# BipolarDAC_16-bit_v01.net
KiCad netlist of a schematic drawn in EAGLE
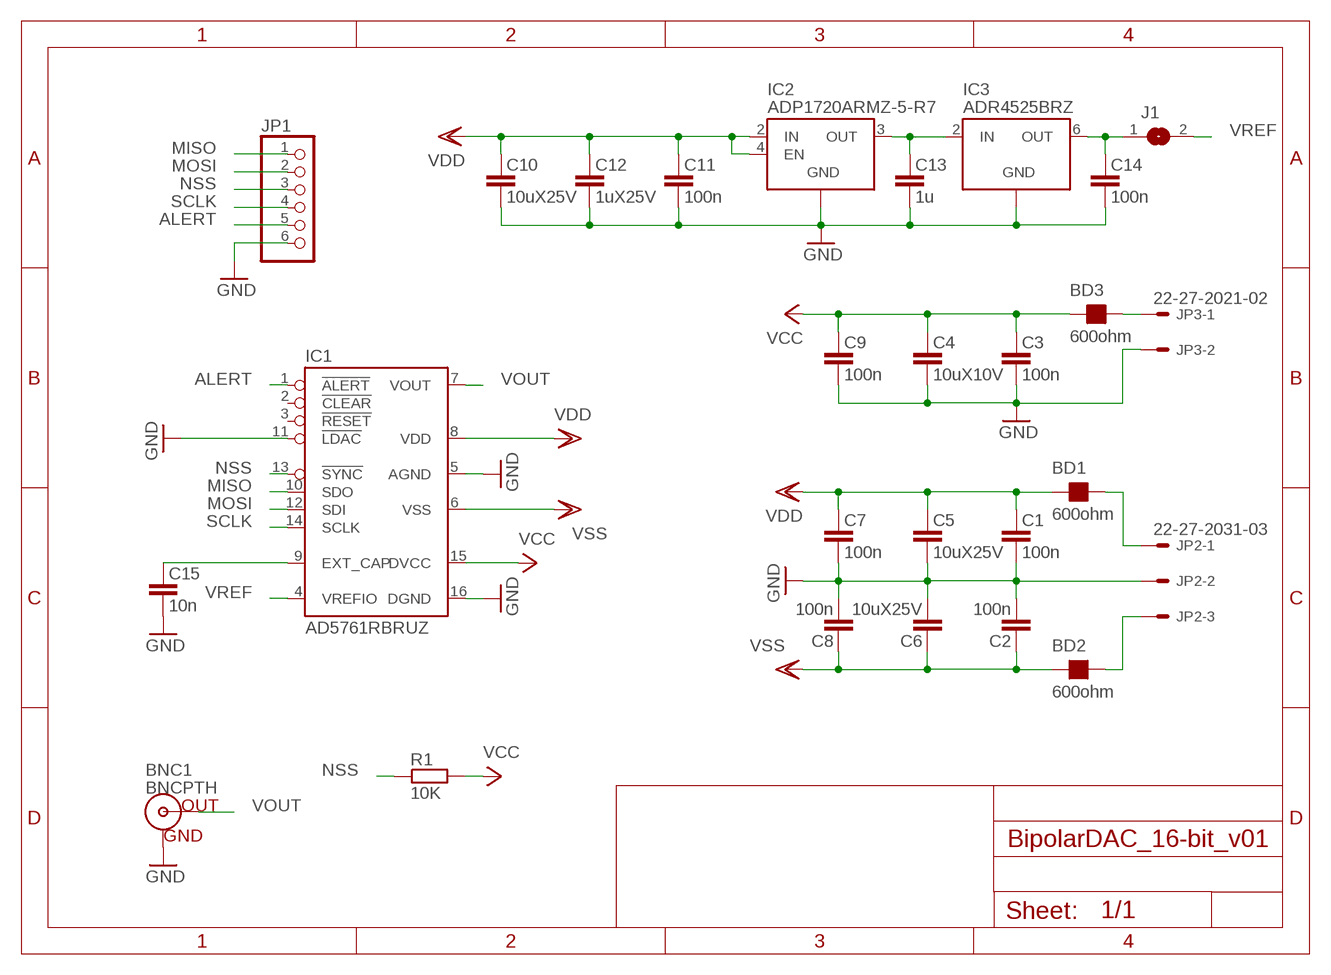
[diagram p0: schematic, sheet 1]

(export (version "E")
  (design (tool "Eeschema 10.0.6"))
  (components
    (comp (ref "BD1")
      (value "600ohm")
      (footprint "eagle-import:L0805")
      (libsource (lib "eagle-import") (part "FB_0805"))
    )
    (comp (ref "BD2")
      (value "600ohm")
      (footprint "eagle-import:L0805")
      (libsource (lib "eagle-import") (part "FB_0805"))
    )
    (comp (ref "BD3")
      (value "600ohm")
      (footprint "eagle-import:L0805")
      (libsource (lib "eagle-import") (part "FB_0805"))
    )
    (comp (ref "BNC1")
      (value "BNCPTH")
      (footprint "eagle-import:BNC")
      (libsource (lib "eagle-import") (part "BNCPTH"))
    )
    (comp (ref "C1")
      (value "100n")
      (footprint "eagle-import:C0603G")
      (libsource (lib "eagle-import") (part "C_EU_C0603G"))
    )
    (comp (ref "C2")
      (value "100n")
      (footprint "eagle-import:C0603G")
      (libsource (lib "eagle-import") (part "C_EU_C0603G"))
    )
    (comp (ref "C3")
      (value "100n")
      (footprint "eagle-import:C0402G")
      (libsource (lib "eagle-import") (part "C_EU_C0402G"))
    )
    (comp (ref "C4")
      (value "10uX10V")
      (footprint "eagle-import:C0805G")
      (libsource (lib "eagle-import") (part "C_EU_C0805G"))
    )
    (comp (ref "C5")
      (value "10uX25V")
      (footprint "eagle-import:C1206G")
      (libsource (lib "eagle-import") (part "C_EU_C1206G"))
    )
    (comp (ref "C6")
      (value "10uX25V")
      (footprint "eagle-import:C1206G")
      (libsource (lib "eagle-import") (part "C_EU_C1206G"))
    )
    (comp (ref "C7")
      (value "100n")
      (footprint "eagle-import:C0603G")
      (libsource (lib "eagle-import") (part "C_EU_C0603G"))
    )
    (comp (ref "C8")
      (value "100n")
      (footprint "eagle-import:C0603G")
      (libsource (lib "eagle-import") (part "C_EU_C0603G"))
    )
    (comp (ref "C9")
      (value "100n")
      (footprint "eagle-import:C0402G")
      (libsource (lib "eagle-import") (part "C_EU_C0402G"))
    )
    (comp (ref "C10")
      (value "10uX25V")
      (footprint "eagle-import:C1206G")
      (libsource (lib "eagle-import") (part "C_EU_C1206G"))
    )
    (comp (ref "C11")
      (value "100n")
      (footprint "eagle-import:C0603G")
      (libsource (lib "eagle-import") (part "C_EU_C0603G"))
    )
    (comp (ref "C12")
      (value "1uX25V")
      (footprint "eagle-import:C0603G")
      (libsource (lib "eagle-import") (part "C_EU_C0603G"))
    )
    (comp (ref "C13")
      (value "1u")
      (footprint "eagle-import:C0603G")
      (libsource (lib "eagle-import") (part "C_EU_C0603G"))
    )
    (comp (ref "C14")
      (value "100n")
      (footprint "eagle-import:C0603G")
      (libsource (lib "eagle-import") (part "C_EU_C0603G"))
    )
    (comp (ref "C15")
      (value "10n")
      (footprint "eagle-import:C0603G")
      (libsource (lib "eagle-import") (part "C_EU_C0603G"))
    )
    (comp (ref "IC1")
      (value "AD5761RBRUZ")
      (footprint "eagle-import:TSSOP16")
      (libsource (lib "eagle-import") (part "AD5761RBRUZ"))
    )
    (comp (ref "IC2")
      (value "ADP1720ARMZ-5-R7")
      (footprint "eagle-import:MSOP8")
      (libsource (lib "eagle-import") (part "ADP1720ARMZ-5-R7"))
    )
    (comp (ref "IC3")
      (value "ADR4525BRZ")
      (footprint "eagle-import:SOIC-8")
      (libsource (lib "eagle-import") (part "ADR4525BRZ"))
    )
    (comp (ref "J1")
      (value "SJS")
      (footprint "eagle-import:SJS")
      (libsource (lib "eagle-import") (part "SJS"))
    )
    (comp (ref "JP1")
      (value "PINHD-1X6")
      (footprint "eagle-import:1X06")
      (libsource (lib "eagle-import") (part "PINHD-1X6"))
    )
    (comp (ref "JP2")
      (value "22-27-2031-03")
      (footprint "eagle-import:6410-03")
      (libsource (lib "eagle-import") (part "22-?-0327-2031"))
    )
    (comp (ref "JP3")
      (value "22-27-2021-02")
      (footprint "eagle-import:6410-02")
      (libsource (lib "eagle-import") (part "22-?-0227-2021"))
    )
    (comp (ref "R1")
      (value "10K")
      (footprint "eagle-import:R0603G")
      (libsource (lib "eagle-import") (part "R_EU_R0603G"))
    )
  )
  (nets
    (net (code "1") (name "/ALERT") (class "Default")
      (node (ref "IC1") (pin "1") (pinfunction "~{ALERT}_1") (pintype "output"))
      (node (ref "JP1") (pin "5") (pinfunction "5_5") (pintype "passive"))
    )
    (net (code "2") (name "/MISO") (class "Default")
      (node (ref "IC1") (pin "10") (pinfunction "SDO_10") (pintype "output"))
      (node (ref "JP1") (pin "1") (pinfunction "1_1") (pintype "passive"))
    )
    (net (code "3") (name "/MOSI") (class "Default")
      (node (ref "IC1") (pin "12") (pinfunction "SDI_12") (pintype "input"))
      (node (ref "JP1") (pin "2") (pinfunction "2_2") (pintype "passive"))
    )
    (net (code "4") (name "/NSS") (class "Default")
      (node (ref "IC1") (pin "13") (pinfunction "~{SYNC}_13") (pintype "input"))
      (node (ref "JP1") (pin "3") (pinfunction "3_3") (pintype "passive"))
      (node (ref "R1") (pin "1") (pinfunction "1_1") (pintype "passive"))
    )
    (net (code "5") (name "/SCLK") (class "Default")
      (node (ref "IC1") (pin "14") (pinfunction "SCLK_14") (pintype "input"))
      (node (ref "JP1") (pin "4") (pinfunction "4_4") (pintype "passive"))
    )
    (net (code "6") (name "/VOUT") (class "Default")
      (node (ref "BNC1") (pin "S") (pinfunction "OUT_S") (pintype "bidirectional"))
      (node (ref "IC1") (pin "7") (pinfunction "VOUT_7") (pintype "output"))
    )
    (net (code "7") (name "/VREF") (class "Default")
      (node (ref "IC1") (pin "4") (pinfunction "VREFIO_4") (pintype "bidirectional"))
      (node (ref "J1") (pin "2") (pinfunction "2_2") (pintype "passive"))
    )
    (net (code "8") (name "GND") (class "Default")
      (node (ref "BNC1") (pin "GND") (pinfunction "GND_GND") (pintype "bidirectional"))
      (node (ref "C1") (pin "2") (pinfunction "2_2") (pintype "passive"))
      (node (ref "C10") (pin "2") (pinfunction "2_2") (pintype "passive"))
      (node (ref "C11") (pin "2") (pinfunction "2_2") (pintype "passive"))
      (node (ref "C12") (pin "2") (pinfunction "2_2") (pintype "passive"))
      (node (ref "C13") (pin "2") (pinfunction "2_2") (pintype "passive"))
      (node (ref "C14") (pin "2") (pinfunction "2_2") (pintype "passive"))
      (node (ref "C15") (pin "2") (pinfunction "2_2") (pintype "passive"))
      (node (ref "C2") (pin "2") (pinfunction "2_2") (pintype "passive"))
      (node (ref "C3") (pin "2") (pinfunction "2_2") (pintype "passive"))
      (node (ref "C4") (pin "2") (pinfunction "2_2") (pintype "passive"))
      (node (ref "C5") (pin "2") (pinfunction "2_2") (pintype "passive"))
      (node (ref "C6") (pin "2") (pinfunction "2_2") (pintype "passive"))
      (node (ref "C7") (pin "2") (pinfunction "2_2") (pintype "passive"))
      (node (ref "C8") (pin "2") (pinfunction "2_2") (pintype "passive"))
      (node (ref "C9") (pin "2") (pinfunction "2_2") (pintype "passive"))
      (node (ref "IC1") (pin "11") (pinfunction "~{LDAC}_11") (pintype "input"))
      (node (ref "IC1") (pin "16") (pinfunction "DGND_16") (pintype "power_in"))
      (node (ref "IC1") (pin "5") (pinfunction "AGND_5") (pintype "power_in"))
      (node (ref "IC2") (pin "1") (pinfunction "GND_1") (pintype "power_in"))
      (node (ref "IC2") (pin "5") (pinfunction "GND_5") (pintype "power_in"))
      (node (ref "IC2") (pin "6") (pinfunction "GND_6") (pintype "power_in"))
      (node (ref "IC2") (pin "7") (pinfunction "GND_7") (pintype "power_in"))
      (node (ref "IC2") (pin "8") (pinfunction "GND_8") (pintype "power_in"))
      (node (ref "IC3") (pin "4") (pinfunction "GND_4") (pintype "power_in"))
      (node (ref "JP1") (pin "6") (pinfunction "6_6") (pintype "passive"))
      (node (ref "JP2") (pin "2") (pinfunction "S_2") (pintype "passive"))
      (node (ref "JP3") (pin "2") (pinfunction "S_2") (pintype "passive"))
    )
    (net (code "9") (name "Net-(IC1-EXT_CAP)") (class "Default")
      (node (ref "C15") (pin "1") (pinfunction "1_1") (pintype "passive"))
      (node (ref "IC1") (pin "9") (pinfunction "EXT_CAP_9") (pintype "output"))
    )
    (net (code "10") (name "Net-(IC2-OUT)") (class "Default")
      (node (ref "C13") (pin "1") (pinfunction "1_1") (pintype "passive"))
      (node (ref "IC2") (pin "3") (pinfunction "OUT_3") (pintype "power_in"))
      (node (ref "IC3") (pin "2") (pinfunction "IN_2") (pintype "power_in"))
    )
    (net (code "11") (name "Net-(IC3-OUT)") (class "Default")
      (node (ref "C14") (pin "1") (pinfunction "1_1") (pintype "passive"))
      (node (ref "IC3") (pin "6") (pinfunction "OUT_6") (pintype "power_in"))
      (node (ref "J1") (pin "1") (pinfunction "1_1") (pintype "passive"))
    )
    (net (code "12") (name "Net-(JP2A-S)") (class "Default")
      (node (ref "BD1") (pin "2") (pinfunction "2_2") (pintype "passive"))
      (node (ref "JP2") (pin "1") (pinfunction "S_1") (pintype "passive"))
    )
    (net (code "13") (name "Net-(JP2C-S)") (class "Default")
      (node (ref "BD2") (pin "2") (pinfunction "2_2") (pintype "passive"))
      (node (ref "JP2") (pin "3") (pinfunction "S_3") (pintype "passive"))
    )
    (net (code "14") (name "Net-(JP3A-S)") (class "Default")
      (node (ref "BD3") (pin "2") (pinfunction "2_2") (pintype "passive"))
      (node (ref "JP3") (pin "1") (pinfunction "S_1") (pintype "passive"))
    )
    (net (code "15") (name "VCC") (class "Default")
      (node (ref "BD3") (pin "1") (pinfunction "1_1") (pintype "passive"))
      (node (ref "C3") (pin "1") (pinfunction "1_1") (pintype "passive"))
      (node (ref "C4") (pin "1") (pinfunction "1_1") (pintype "passive"))
      (node (ref "C9") (pin "1") (pinfunction "1_1") (pintype "passive"))
      (node (ref "IC1") (pin "15") (pinfunction "DVCC_15") (pintype "power_in"))
      (node (ref "R1") (pin "2") (pinfunction "2_2") (pintype "passive"))
    )
    (net (code "16") (name "VDD") (class "Default")
      (node (ref "BD1") (pin "1") (pinfunction "1_1") (pintype "passive"))
      (node (ref "C1") (pin "1") (pinfunction "1_1") (pintype "passive"))
      (node (ref "C10") (pin "1") (pinfunction "1_1") (pintype "passive"))
      (node (ref "C11") (pin "1") (pinfunction "1_1") (pintype "passive"))
      (node (ref "C12") (pin "1") (pinfunction "1_1") (pintype "passive"))
      (node (ref "C5") (pin "1") (pinfunction "1_1") (pintype "passive"))
      (node (ref "C7") (pin "1") (pinfunction "1_1") (pintype "passive"))
      (node (ref "IC1") (pin "8") (pinfunction "VDD_8") (pintype "power_in"))
      (node (ref "IC2") (pin "2") (pinfunction "IN_2") (pintype "power_in"))
      (node (ref "IC2") (pin "4") (pinfunction "EN_4") (pintype "input"))
    )
    (net (code "17") (name "VSS") (class "Default")
      (node (ref "BD2") (pin "1") (pinfunction "1_1") (pintype "passive"))
      (node (ref "C2") (pin "1") (pinfunction "1_1") (pintype "passive"))
      (node (ref "C6") (pin "1") (pinfunction "1_1") (pintype "passive"))
      (node (ref "C8") (pin "1") (pinfunction "1_1") (pintype "passive"))
      (node (ref "IC1") (pin "6") (pinfunction "VSS_6") (pintype "power_in"))
    )
    (net (code "18") (name "unconnected-(IC1-~{CLEAR}-Pad2)") (class "Default")
      (node (ref "IC1") (pin "2") (pinfunction "~{CLEAR}_2") (pintype "input"))
    )
    (net (code "19") (name "unconnected-(IC1-~{RESET}-Pad3)") (class "Default")
      (node (ref "IC1") (pin "3") (pinfunction "~{RESET}_3") (pintype "input"))
    )
  )
)
